# IC_left.net
KiCad netlist of a schematic drawn in Altium Designer
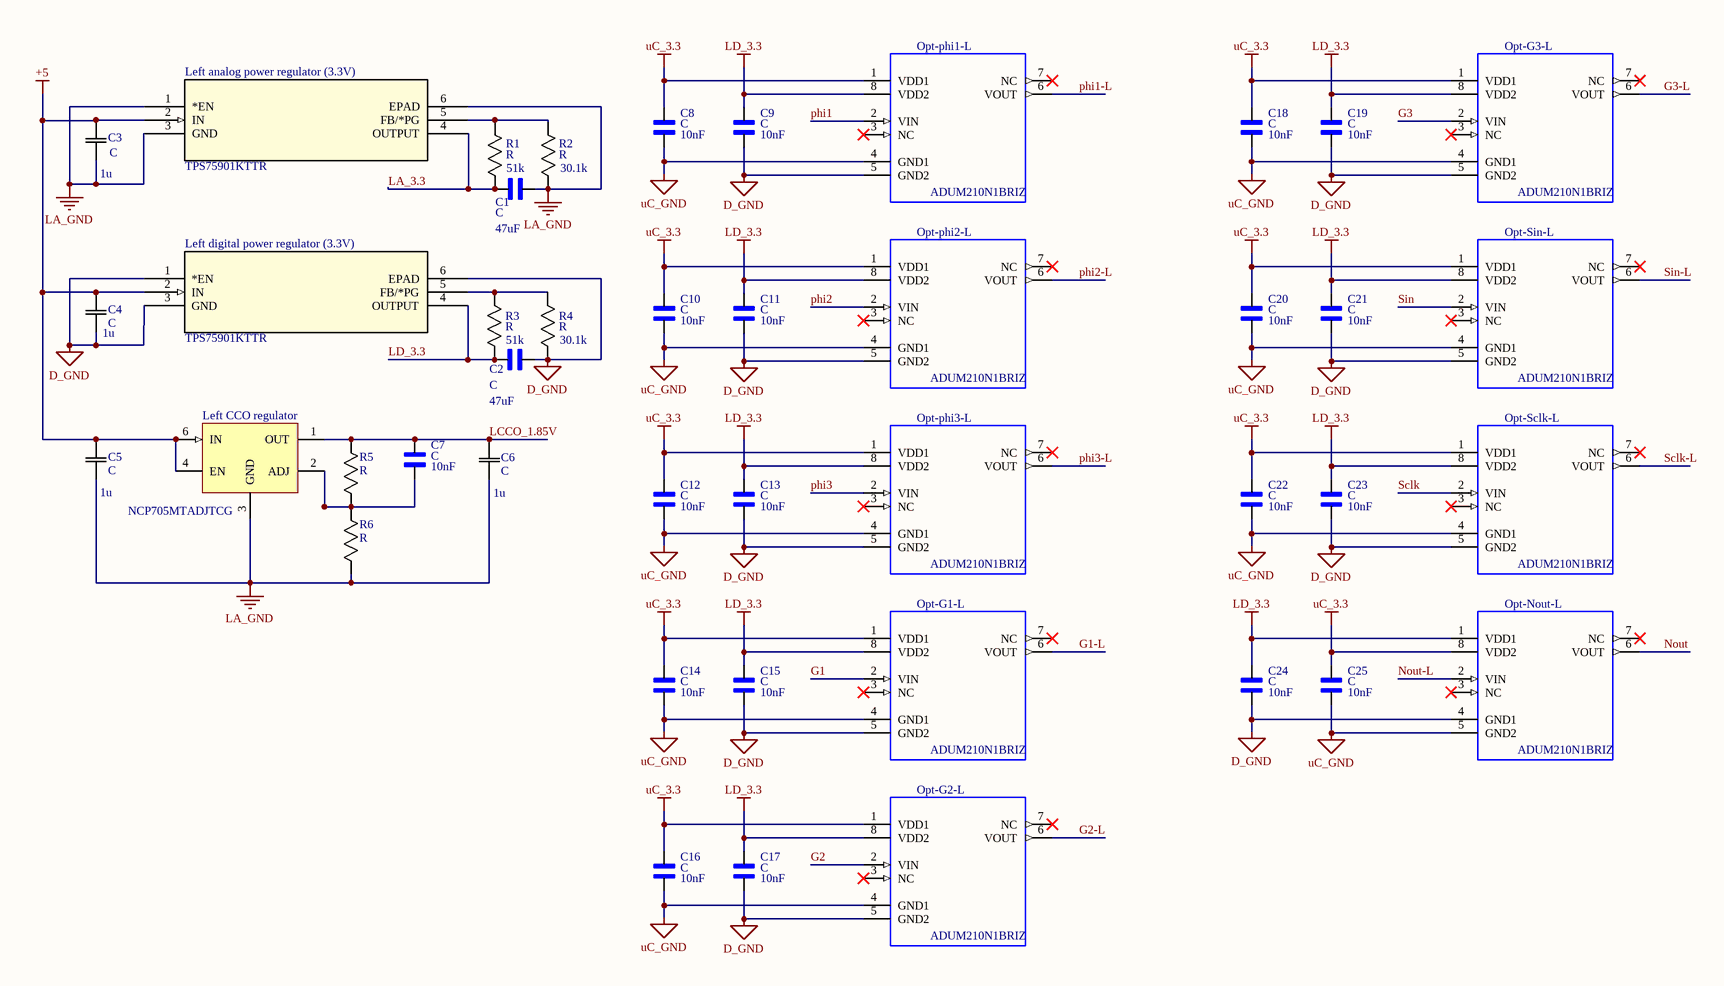
[diagram p0: IC left.SchDoc]

(export (version "E")
  (design (tool "Eeschema 10.0.6"))
  (components
    (comp (ref "C1")
      (value "C")
      (footprint "CAPC1608X9N")
      (description "Multilayer Ceramic Capacitors - 47uF 4V X5R 20% Pad SMD 0603 85C T/R")
      (fields
        (field (name "DIGI-KEY_PART_NUMBER") "490-13246-1-ND")
        (field (name "MF") "Murata")
        (field (name "ALTIUM_VALUE") "47uF")
      )
      (libsource (lib "47uF 0603  CAP") (part "GRM188R60G476ME15D"))
    )
    (comp (ref "C2")
      (value "C")
      (footprint "CAPC1608X9N")
      (description "Multilayer Ceramic Capacitors - 47uF 4V X5R 20% Pad SMD 0603 85C T/R")
      (fields
        (field (name "DIGI-KEY_PART_NUMBER") "490-13246-1-ND")
        (field (name "MF") "Murata")
        (field (name "ALTIUM_VALUE") "47uF")
      )
      (libsource (lib "47uF 0603  CAP") (part "GRM188R60G476ME15D"))
    )
    (comp (ref "C3")
      (value "C")
      (footprint "CAP_GRM_188")
      (description "Imported")
      (fields
        (field (name "ALTIUM_VALUE") "1u")
        (field (name "MANUFACTURER PART NUMBER") "GRM188R60J105KA01D")
      )
      (libsource (lib "1uF 0603 CAP") (part "GRM188R60J105KA0"))
    )
    (comp (ref "C4")
      (value "C")
      (footprint "CAP_GRM_188")
      (description "Imported")
      (fields
        (field (name "ALTIUM_VALUE") "1u")
        (field (name "MANUFACTURER PART NUMBER") "GRM188R60J105KA01D")
      )
      (libsource (lib "1uF 0603 CAP") (part "GRM188R60J105KA0"))
    )
    (comp (ref "C5")
      (value "C")
      (footprint "CAP_GRM_188")
      (description "Imported")
      (fields
        (field (name "ALTIUM_VALUE") "1u")
        (field (name "MANUFACTURER PART NUMBER") "GRM188R60J105KA01D")
      )
      (libsource (lib "1uF 0603 CAP") (part "GRM188R60J105KA0"))
    )
    (comp (ref "C6")
      (value "C")
      (footprint "CAP_GRM_188")
      (description "Imported")
      (fields
        (field (name "ALTIUM_VALUE") "1u")
        (field (name "MANUFACTURER PART NUMBER") "GRM188R60J105KA01D")
      )
      (libsource (lib "1uF 0603 CAP") (part "GRM188R60J105KA0"))
    )
    (comp (ref "C7")
      (value "C")
      (footprint "CAPC1608X9N")
      (description "Multilayer Ceramic Capacitor, GRM Series, 0.01 F, 5%, C0G / NP0, 50 V, 0603 [1608 Metric]")
      (fields
        (field (name "MF") "Murata")
        (field (name "DIGI-KEY_PART_NUMBER") "490-9666-1-ND")
        (field (name "ALTIUM_VALUE") "10nF")
      )
      (libsource (lib "10nF 0603 CAP") (part "GRM1885C1H103JA01D"))
    )
    (comp (ref "C8")
      (value "C")
      (footprint "CAPC1608X9N")
      (description "Multilayer Ceramic Capacitor, GRM Series, 0.01 F, 5%, C0G / NP0, 50 V, 0603 [1608 Metric]")
      (fields
        (field (name "MF") "Murata")
        (field (name "DIGI-KEY_PART_NUMBER") "490-9666-1-ND")
        (field (name "ALTIUM_VALUE") "10nF")
      )
      (libsource (lib "10nF 0603 CAP") (part "GRM1885C1H103JA01D"))
    )
    (comp (ref "C9")
      (value "C")
      (footprint "CAPC1608X9N")
      (description "Multilayer Ceramic Capacitor, GRM Series, 0.01 F, 5%, C0G / NP0, 50 V, 0603 [1608 Metric]")
      (fields
        (field (name "MF") "Murata")
        (field (name "DIGI-KEY_PART_NUMBER") "490-9666-1-ND")
        (field (name "ALTIUM_VALUE") "10nF")
      )
      (libsource (lib "10nF 0603 CAP") (part "GRM1885C1H103JA01D"))
    )
    (comp (ref "C10")
      (value "C")
      (footprint "CAPC1608X9N")
      (description "Multilayer Ceramic Capacitor, GRM Series, 0.01 F, 5%, C0G / NP0, 50 V, 0603 [1608 Metric]")
      (fields
        (field (name "MF") "Murata")
        (field (name "DIGI-KEY_PART_NUMBER") "490-9666-1-ND")
        (field (name "ALTIUM_VALUE") "10nF")
      )
      (libsource (lib "10nF 0603 CAP") (part "GRM1885C1H103JA01D"))
    )
    (comp (ref "C11")
      (value "C")
      (footprint "CAPC1608X9N")
      (description "Multilayer Ceramic Capacitor, GRM Series, 0.01 F, 5%, C0G / NP0, 50 V, 0603 [1608 Metric]")
      (fields
        (field (name "MF") "Murata")
        (field (name "DIGI-KEY_PART_NUMBER") "490-9666-1-ND")
        (field (name "ALTIUM_VALUE") "10nF")
      )
      (libsource (lib "10nF 0603 CAP") (part "GRM1885C1H103JA01D"))
    )
    (comp (ref "C12")
      (value "C")
      (footprint "CAPC1608X9N")
      (description "Multilayer Ceramic Capacitor, GRM Series, 0.01 F, 5%, C0G / NP0, 50 V, 0603 [1608 Metric]")
      (fields
        (field (name "MF") "Murata")
        (field (name "DIGI-KEY_PART_NUMBER") "490-9666-1-ND")
        (field (name "ALTIUM_VALUE") "10nF")
      )
      (libsource (lib "10nF 0603 CAP") (part "GRM1885C1H103JA01D"))
    )
    (comp (ref "C13")
      (value "C")
      (footprint "CAPC1608X9N")
      (description "Multilayer Ceramic Capacitor, GRM Series, 0.01 F, 5%, C0G / NP0, 50 V, 0603 [1608 Metric]")
      (fields
        (field (name "MF") "Murata")
        (field (name "DIGI-KEY_PART_NUMBER") "490-9666-1-ND")
        (field (name "ALTIUM_VALUE") "10nF")
      )
      (libsource (lib "10nF 0603 CAP") (part "GRM1885C1H103JA01D"))
    )
    (comp (ref "C14")
      (value "C")
      (footprint "CAPC1608X9N")
      (description "Multilayer Ceramic Capacitor, GRM Series, 0.01 F, 5%, C0G / NP0, 50 V, 0603 [1608 Metric]")
      (fields
        (field (name "MF") "Murata")
        (field (name "DIGI-KEY_PART_NUMBER") "490-9666-1-ND")
        (field (name "ALTIUM_VALUE") "10nF")
      )
      (libsource (lib "10nF 0603 CAP") (part "GRM1885C1H103JA01D"))
    )
    (comp (ref "C15")
      (value "C")
      (footprint "CAPC1608X9N")
      (description "Multilayer Ceramic Capacitor, GRM Series, 0.01 F, 5%, C0G / NP0, 50 V, 0603 [1608 Metric]")
      (fields
        (field (name "MF") "Murata")
        (field (name "DIGI-KEY_PART_NUMBER") "490-9666-1-ND")
        (field (name "ALTIUM_VALUE") "10nF")
      )
      (libsource (lib "10nF 0603 CAP") (part "GRM1885C1H103JA01D"))
    )
    (comp (ref "C16")
      (value "C")
      (footprint "CAPC1608X9N")
      (description "Multilayer Ceramic Capacitor, GRM Series, 0.01 F, 5%, C0G / NP0, 50 V, 0603 [1608 Metric]")
      (fields
        (field (name "MF") "Murata")
        (field (name "DIGI-KEY_PART_NUMBER") "490-9666-1-ND")
        (field (name "ALTIUM_VALUE") "10nF")
      )
      (libsource (lib "10nF 0603 CAP") (part "GRM1885C1H103JA01D"))
    )
    (comp (ref "C17")
      (value "C")
      (footprint "CAPC1608X9N")
      (description "Multilayer Ceramic Capacitor, GRM Series, 0.01 F, 5%, C0G / NP0, 50 V, 0603 [1608 Metric]")
      (fields
        (field (name "MF") "Murata")
        (field (name "DIGI-KEY_PART_NUMBER") "490-9666-1-ND")
        (field (name "ALTIUM_VALUE") "10nF")
      )
      (libsource (lib "10nF 0603 CAP") (part "GRM1885C1H103JA01D"))
    )
    (comp (ref "C18")
      (value "C")
      (footprint "CAPC1608X9N")
      (description "Multilayer Ceramic Capacitor, GRM Series, 0.01 F, 5%, C0G / NP0, 50 V, 0603 [1608 Metric]")
      (fields
        (field (name "MF") "Murata")
        (field (name "DIGI-KEY_PART_NUMBER") "490-9666-1-ND")
        (field (name "ALTIUM_VALUE") "10nF")
      )
      (libsource (lib "10nF 0603 CAP") (part "GRM1885C1H103JA01D"))
    )
    (comp (ref "C19")
      (value "C")
      (footprint "CAPC1608X9N")
      (description "Multilayer Ceramic Capacitor, GRM Series, 0.01 F, 5%, C0G / NP0, 50 V, 0603 [1608 Metric]")
      (fields
        (field (name "MF") "Murata")
        (field (name "DIGI-KEY_PART_NUMBER") "490-9666-1-ND")
        (field (name "ALTIUM_VALUE") "10nF")
      )
      (libsource (lib "10nF 0603 CAP") (part "GRM1885C1H103JA01D"))
    )
    (comp (ref "C20")
      (value "C")
      (footprint "CAPC1608X9N")
      (description "Multilayer Ceramic Capacitor, GRM Series, 0.01 F, 5%, C0G / NP0, 50 V, 0603 [1608 Metric]")
      (fields
        (field (name "MF") "Murata")
        (field (name "DIGI-KEY_PART_NUMBER") "490-9666-1-ND")
        (field (name "ALTIUM_VALUE") "10nF")
      )
      (libsource (lib "10nF 0603 CAP") (part "GRM1885C1H103JA01D"))
    )
    (comp (ref "C21")
      (value "C")
      (footprint "CAPC1608X9N")
      (description "Multilayer Ceramic Capacitor, GRM Series, 0.01 F, 5%, C0G / NP0, 50 V, 0603 [1608 Metric]")
      (fields
        (field (name "MF") "Murata")
        (field (name "DIGI-KEY_PART_NUMBER") "490-9666-1-ND")
        (field (name "ALTIUM_VALUE") "10nF")
      )
      (libsource (lib "10nF 0603 CAP") (part "GRM1885C1H103JA01D"))
    )
    (comp (ref "C22")
      (value "C")
      (footprint "CAPC1608X9N")
      (description "Multilayer Ceramic Capacitor, GRM Series, 0.01 F, 5%, C0G / NP0, 50 V, 0603 [1608 Metric]")
      (fields
        (field (name "MF") "Murata")
        (field (name "DIGI-KEY_PART_NUMBER") "490-9666-1-ND")
        (field (name "ALTIUM_VALUE") "10nF")
      )
      (libsource (lib "10nF 0603 CAP") (part "GRM1885C1H103JA01D"))
    )
    (comp (ref "C23")
      (value "C")
      (footprint "CAPC1608X9N")
      (description "Multilayer Ceramic Capacitor, GRM Series, 0.01 F, 5%, C0G / NP0, 50 V, 0603 [1608 Metric]")
      (fields
        (field (name "MF") "Murata")
        (field (name "DIGI-KEY_PART_NUMBER") "490-9666-1-ND")
        (field (name "ALTIUM_VALUE") "10nF")
      )
      (libsource (lib "10nF 0603 CAP") (part "GRM1885C1H103JA01D"))
    )
    (comp (ref "C24")
      (value "C")
      (footprint "CAPC1608X9N")
      (description "Multilayer Ceramic Capacitor, GRM Series, 0.01 F, 5%, C0G / NP0, 50 V, 0603 [1608 Metric]")
      (fields
        (field (name "MF") "Murata")
        (field (name "DIGI-KEY_PART_NUMBER") "490-9666-1-ND")
        (field (name "ALTIUM_VALUE") "10nF")
      )
      (libsource (lib "10nF 0603 CAP") (part "GRM1885C1H103JA01D"))
    )
    (comp (ref "C25")
      (value "C")
      (footprint "CAPC1608X9N")
      (description "Multilayer Ceramic Capacitor, GRM Series, 0.01 F, 5%, C0G / NP0, 50 V, 0603 [1608 Metric]")
      (fields
        (field (name "MF") "Murata")
        (field (name "DIGI-KEY_PART_NUMBER") "490-9666-1-ND")
        (field (name "ALTIUM_VALUE") "10nF")
      )
      (libsource (lib "10nF 0603 CAP") (part "GRM1885C1H103JA01D"))
    )
    (comp (ref "Left analog power regulator (3.3V)")
      (value "TPS75901KTTR")
      (footprint "TO-263-5")
      (description "Imported")
      (fields (field (name "MANUFACTURER") "Texas Instruments"))
      (libsource (lib "TPS75901KTTR") (part "TPS75901KTTR"))
    )
    (comp (ref "Left CCO regulator")
      (value "NCP705MTADJTCG")
      (footprint "WDFN6")
      (description "500 mA, Ultra-Low  Quiescent Current, IQ 13 A,  Ultra-Low Noise, LDO  Voltage Regulator")
      (fields (field (name "MANUFACTURER") "ON Semiconductor"))
      (libsource (lib "NCP705MTADJTCG") (part "NCP705MTADJTCG"))
    )
    (comp (ref "Left digital power regulator (3.3V)")
      (value "TPS75901KTTR")
      (footprint "TO-263-5")
      (description "Imported")
      (fields (field (name "MANUFACTURER") "Texas Instruments"))
      (libsource (lib "TPS75901KTTR") (part "TPS75901KTTR"))
    )
    (comp (ref "Opt-G1-L")
      (value "ADUM210N1BRIZ")
      (footprint "SOIC127P1150X330-8N")
      (description "Digital isolator 1-CH 8-Pin SOIC T/R")
      (fields (field (name "DIGI-KEY_PART_NUMBER") "ADUM210N1BRIZ-ND") (field (name "MF") "Analog Devices"))
      (libsource (lib "ADUM210N1BRIZ") (part "ADUM210N1BRIZ"))
    )
    (comp (ref "Opt-G2-L")
      (value "ADUM210N1BRIZ")
      (footprint "SOIC127P1150X330-8N")
      (description "Digital isolator 1-CH 8-Pin SOIC T/R")
      (fields (field (name "DIGI-KEY_PART_NUMBER") "ADUM210N1BRIZ-ND") (field (name "MF") "Analog Devices"))
      (libsource (lib "ADUM210N1BRIZ") (part "ADUM210N1BRIZ"))
    )
    (comp (ref "Opt-G3-L")
      (value "ADUM210N1BRIZ")
      (footprint "SOIC127P1150X330-8N")
      (description "Digital isolator 1-CH 8-Pin SOIC T/R")
      (fields (field (name "DIGI-KEY_PART_NUMBER") "ADUM210N1BRIZ-ND") (field (name "MF") "Analog Devices"))
      (libsource (lib "ADUM210N1BRIZ") (part "ADUM210N1BRIZ"))
    )
    (comp (ref "Opt-Nout-L")
      (value "ADUM210N1BRIZ")
      (footprint "SOIC127P1150X330-8N")
      (description "Digital isolator 1-CH 8-Pin SOIC T/R")
      (fields (field (name "DIGI-KEY_PART_NUMBER") "ADUM210N1BRIZ-ND") (field (name "MF") "Analog Devices"))
      (libsource (lib "ADUM210N1BRIZ") (part "ADUM210N1BRIZ"))
    )
    (comp (ref "Opt-phi1-L")
      (value "ADUM210N1BRIZ")
      (footprint "SOIC127P1150X330-8N")
      (description "Digital isolator 1-CH 8-Pin SOIC T/R")
      (fields (field (name "DIGI-KEY_PART_NUMBER") "ADUM210N1BRIZ-ND") (field (name "MF") "Analog Devices"))
      (libsource (lib "ADUM210N1BRIZ") (part "ADUM210N1BRIZ"))
    )
    (comp (ref "Opt-phi2-L")
      (value "ADUM210N1BRIZ")
      (footprint "SOIC127P1150X330-8N")
      (description "Digital isolator 1-CH 8-Pin SOIC T/R")
      (fields (field (name "DIGI-KEY_PART_NUMBER") "ADUM210N1BRIZ-ND") (field (name "MF") "Analog Devices"))
      (libsource (lib "ADUM210N1BRIZ") (part "ADUM210N1BRIZ"))
    )
    (comp (ref "Opt-phi3-L")
      (value "ADUM210N1BRIZ")
      (footprint "SOIC127P1150X330-8N")
      (description "Digital isolator 1-CH 8-Pin SOIC T/R")
      (fields (field (name "DIGI-KEY_PART_NUMBER") "ADUM210N1BRIZ-ND") (field (name "MF") "Analog Devices"))
      (libsource (lib "ADUM210N1BRIZ") (part "ADUM210N1BRIZ"))
    )
    (comp (ref "Opt-Sclk-L")
      (value "ADUM210N1BRIZ")
      (footprint "SOIC127P1150X330-8N")
      (description "Digital isolator 1-CH 8-Pin SOIC T/R")
      (fields (field (name "DIGI-KEY_PART_NUMBER") "ADUM210N1BRIZ-ND") (field (name "MF") "Analog Devices"))
      (libsource (lib "ADUM210N1BRIZ") (part "ADUM210N1BRIZ"))
    )
    (comp (ref "Opt-Sin-L")
      (value "ADUM210N1BRIZ")
      (footprint "SOIC127P1150X330-8N")
      (description "Digital isolator 1-CH 8-Pin SOIC T/R")
      (fields (field (name "DIGI-KEY_PART_NUMBER") "ADUM210N1BRIZ-ND") (field (name "MF") "Analog Devices"))
      (libsource (lib "ADUM210N1BRIZ") (part "ADUM210N1BRIZ"))
    )
    (comp (ref "R1")
      (value "R")
      (footprint "RES_0816")
      (description "Imported")
      (fields (field (name "ALTIUM_VALUE") "51k") (field (name "MANUFACTURER PART NUMBER") "RR0816P-513-D"))
      (libsource (lib "51kOhm 0603 RES") (part "RR0816P-513-D"))
    )
    (comp (ref "R2")
      (value "R")
      (footprint "RC0603N")
      (description "Imported")
      (fields
        (field (name "ALTIUM_VALUE") "30.1k")
        (field (name "MANUFACTURER PART NUMBER") "RT0603BRD0730K1L")
      )
      (libsource (lib "30.1kOhm 0603 RES") (part "RT0603BRD0730K1L"))
    )
    (comp (ref "R3")
      (value "R")
      (footprint "RES_0816")
      (description "Imported")
      (fields (field (name "ALTIUM_VALUE") "51k") (field (name "MANUFACTURER PART NUMBER") "RR0816P-513-D"))
      (libsource (lib "51kOhm 0603 RES") (part "RR0816P-513-D"))
    )
    (comp (ref "R4")
      (value "R")
      (footprint "RC0603N")
      (description "Imported")
      (fields
        (field (name "ALTIUM_VALUE") "30.1k")
        (field (name "MANUFACTURER PART NUMBER") "RT0603BRD0730K1L")
      )
      (libsource (lib "30.1kOhm 0603 RES") (part "RT0603BRD0730K1L"))
    )
    (comp (ref "R5")
      (value "R")
      (footprint "RC0603N")
      (description "Imported")
      (fields (field (name "MANUFACTURER PART NUMBER") "RC0603FR-07130KL"))
      (libsource (lib "130k 0603 RES") (part "RC0603FR-07130KL"))
    )
    (comp (ref "R6")
      (value "R")
      (footprint "RC0603N")
      (description "Imported")
      (fields (field (name "MANUFACTURER PART NUMBER") "ERJ-3GEY0R00V"))
      (libsource (lib "98.8k 0603 RES") (part "ERJ-3GEY0R00V"))
    )
  )
  (nets
    (net (code "1") (name "+5") (class "Default")
      (node (ref "C3") (pin "2") (pinfunction "2_2") (pintype "passive"))
      (node (ref "C4") (pin "2") (pinfunction "2_2") (pintype "passive"))
      (node (ref "C5") (pin "2") (pinfunction "2_2") (pintype "passive"))
      (node (ref "Left CCO regulator") (pin "4") (pinfunction "EN_4") (pintype "passive"))
      (node (ref "Left CCO regulator") (pin "6") (pinfunction "IN_6") (pintype "input"))
      (node (ref "Left analog power regulator (3.3V)") (pin "2") (pinfunction "IN_2") (pintype "input"))
      (node (ref "Left digital power regulator (3.3V)") (pin "2") (pinfunction "IN_2") (pintype "input"))
    )
    (net (code "2") (name "/G1") (class "Default")
      (node (ref "Opt-G1-L") (pin "2") (pinfunction "VIN_2") (pintype "input"))
    )
    (net (code "3") (name "/G1-L") (class "Default")
      (node (ref "Opt-G1-L") (pin "6") (pinfunction "VOUT_6") (pintype "output"))
    )
    (net (code "4") (name "/G2") (class "Default")
      (node (ref "Opt-G2-L") (pin "2") (pinfunction "VIN_2") (pintype "input"))
    )
    (net (code "5") (name "/G2-L") (class "Default")
      (node (ref "Opt-G2-L") (pin "6") (pinfunction "VOUT_6") (pintype "output"))
    )
    (net (code "6") (name "/G3") (class "Default")
      (node (ref "Opt-G3-L") (pin "2") (pinfunction "VIN_2") (pintype "input"))
    )
    (net (code "7") (name "/G3-L") (class "Default")
      (node (ref "Opt-G3-L") (pin "6") (pinfunction "VOUT_6") (pintype "output"))
    )
    (net (code "8") (name "/LA_3.3") (class "Default")
      (node (ref "C1") (pin "2") (pinfunction "2_2") (pintype "passive"))
      (node (ref "Left analog power regulator (3.3V)") (pin "4") (pinfunction "OUTPUT_4") (pintype "power_in"))
      (node (ref "R1") (pin "1") (pinfunction "1_1") (pintype "passive"))
    )
    (net (code "9") (name "/LCCO_1.85V") (class "Default")
      (node (ref "C6") (pin "2") (pinfunction "2_2") (pintype "passive"))
      (node (ref "C7") (pin "1") (pinfunction "1_1") (pintype "passive"))
      (node (ref "Left CCO regulator") (pin "1") (pinfunction "OUT_1") (pintype "power_in"))
      (node (ref "R5") (pin "1") (pinfunction "1_1") (pintype "passive"))
    )
    (net (code "10") (name "/Nout") (class "Default")
      (node (ref "Opt-Nout-L") (pin "6") (pinfunction "VOUT_6") (pintype "output"))
    )
    (net (code "11") (name "/Nout-L") (class "Default")
      (node (ref "Opt-Nout-L") (pin "2") (pinfunction "VIN_2") (pintype "input"))
    )
    (net (code "12") (name "/Sclk") (class "Default")
      (node (ref "Opt-Sclk-L") (pin "2") (pinfunction "VIN_2") (pintype "input"))
    )
    (net (code "13") (name "/Sclk-L") (class "Default")
      (node (ref "Opt-Sclk-L") (pin "6") (pinfunction "VOUT_6") (pintype "output"))
    )
    (net (code "14") (name "/Sin") (class "Default")
      (node (ref "Opt-Sin-L") (pin "2") (pinfunction "VIN_2") (pintype "input"))
    )
    (net (code "15") (name "/Sin-L") (class "Default")
      (node (ref "Opt-Sin-L") (pin "6") (pinfunction "VOUT_6") (pintype "output"))
    )
    (net (code "16") (name "/phi1") (class "Default")
      (node (ref "Opt-phi1-L") (pin "2") (pinfunction "VIN_2") (pintype "input"))
    )
    (net (code "17") (name "/phi1-L") (class "Default")
      (node (ref "Opt-phi1-L") (pin "6") (pinfunction "VOUT_6") (pintype "output"))
    )
    (net (code "18") (name "/phi2") (class "Default")
      (node (ref "Opt-phi2-L") (pin "2") (pinfunction "VIN_2") (pintype "input"))
    )
    (net (code "19") (name "/phi2-L") (class "Default")
      (node (ref "Opt-phi2-L") (pin "6") (pinfunction "VOUT_6") (pintype "output"))
    )
    (net (code "20") (name "/phi3") (class "Default")
      (node (ref "Opt-phi3-L") (pin "2") (pinfunction "VIN_2") (pintype "input"))
    )
    (net (code "21") (name "/phi3-L") (class "Default")
      (node (ref "Opt-phi3-L") (pin "6") (pinfunction "VOUT_6") (pintype "output"))
    )
    (net (code "22") (name "D_GND") (class "Default")
      (node (ref "C11") (pin "2") (pinfunction "2_2") (pintype "passive"))
      (node (ref "C13") (pin "2") (pinfunction "2_2") (pintype "passive"))
      (node (ref "C15") (pin "2") (pinfunction "2_2") (pintype "passive"))
      (node (ref "C17") (pin "2") (pinfunction "2_2") (pintype "passive"))
      (node (ref "C19") (pin "2") (pinfunction "2_2") (pintype "passive"))
      (node (ref "C2") (pin "1") (pinfunction "1_1") (pintype "passive"))
      (node (ref "C21") (pin "2") (pinfunction "2_2") (pintype "passive"))
      (node (ref "C23") (pin "2") (pinfunction "2_2") (pintype "passive"))
      (node (ref "C24") (pin "2") (pinfunction "2_2") (pintype "passive"))
      (node (ref "C4") (pin "1") (pinfunction "1_1") (pintype "passive"))
      (node (ref "C9") (pin "2") (pinfunction "2_2") (pintype "passive"))
      (node (ref "Left digital power regulator (3.3V)") (pin "1") (pinfunction "*EN_1") (pintype "passive"))
      (node (ref "Left digital power regulator (3.3V)") (pin "3") (pinfunction "GND_3") (pintype "power_in"))
      (node (ref "Left digital power regulator (3.3V)") (pin "6") (pinfunction "EPAD_6") (pintype "passive"))
      (node (ref "Opt-G1-L") (pin "5") (pinfunction "GND2_5") (pintype "passive"))
      (node (ref "Opt-G2-L") (pin "5") (pinfunction "GND2_5") (pintype "passive"))
      (node (ref "Opt-G3-L") (pin "5") (pinfunction "GND2_5") (pintype "passive"))
      (node (ref "Opt-Nout-L") (pin "4") (pinfunction "GND1_4") (pintype "passive"))
      (node (ref "Opt-Sclk-L") (pin "5") (pinfunction "GND2_5") (pintype "passive"))
      (node (ref "Opt-Sin-L") (pin "5") (pinfunction "GND2_5") (pintype "passive"))
      (node (ref "Opt-phi1-L") (pin "5") (pinfunction "GND2_5") (pintype "passive"))
      (node (ref "Opt-phi2-L") (pin "5") (pinfunction "GND2_5") (pintype "passive"))
      (node (ref "Opt-phi3-L") (pin "5") (pinfunction "GND2_5") (pintype "passive"))
      (node (ref "R4") (pin "2") (pinfunction "2_2") (pintype "passive"))
    )
    (net (code "23") (name "LA_GND") (class "Default")
      (node (ref "C1") (pin "1") (pinfunction "1_1") (pintype "passive"))
      (node (ref "C3") (pin "1") (pinfunction "1_1") (pintype "passive"))
      (node (ref "C5") (pin "1") (pinfunction "1_1") (pintype "passive"))
      (node (ref "C6") (pin "1") (pinfunction "1_1") (pintype "passive"))
      (node (ref "Left CCO regulator") (pin "3") (pinfunction "GND_3") (pintype "power_in"))
      (node (ref "Left analog power regulator (3.3V)") (pin "1") (pinfunction "*EN_1") (pintype "passive"))
      (node (ref "Left analog power regulator (3.3V)") (pin "3") (pinfunction "GND_3") (pintype "power_in"))
      (node (ref "Left analog power regulator (3.3V)") (pin "6") (pinfunction "EPAD_6") (pintype "passive"))
      (node (ref "R2") (pin "2") (pinfunction "2_2") (pintype "passive"))
      (node (ref "R6") (pin "2") (pinfunction "2_2") (pintype "passive"))
    )
    (net (code "24") (name "LD_3.3") (class "Default")
      (node (ref "C11") (pin "1") (pinfunction "1_1") (pintype "passive"))
      (node (ref "C13") (pin "1") (pinfunction "1_1") (pintype "passive"))
      (node (ref "C15") (pin "1") (pinfunction "1_1") (pintype "passive"))
      (node (ref "C17") (pin "1") (pinfunction "1_1") (pintype "passive"))
      (node (ref "C19") (pin "1") (pinfunction "1_1") (pintype "passive"))
      (node (ref "C2") (pin "2") (pinfunction "2_2") (pintype "passive"))
      (node (ref "C21") (pin "1") (pinfunction "1_1") (pintype "passive"))
      (node (ref "C23") (pin "1") (pinfunction "1_1") (pintype "passive"))
      (node (ref "C24") (pin "1") (pinfunction "1_1") (pintype "passive"))
      (node (ref "C9") (pin "1") (pinfunction "1_1") (pintype "passive"))
      (node (ref "Left digital power regulator (3.3V)") (pin "4") (pinfunction "OUTPUT_4") (pintype "power_in"))
      (node (ref "Opt-G1-L") (pin "8") (pinfunction "VDD2_8") (pintype "power_in"))
      (node (ref "Opt-G2-L") (pin "8") (pinfunction "VDD2_8") (pintype "power_in"))
      (node (ref "Opt-G3-L") (pin "8") (pinfunction "VDD2_8") (pintype "power_in"))
      (node (ref "Opt-Nout-L") (pin "1") (pinfunction "VDD1_1") (pintype "power_in"))
      (node (ref "Opt-Sclk-L") (pin "8") (pinfunction "VDD2_8") (pintype "power_in"))
      (node (ref "Opt-Sin-L") (pin "8") (pinfunction "VDD2_8") (pintype "power_in"))
      (node (ref "Opt-phi1-L") (pin "8") (pinfunction "VDD2_8") (pintype "power_in"))
      (node (ref "Opt-phi2-L") (pin "8") (pinfunction "VDD2_8") (pintype "power_in"))
      (node (ref "Opt-phi3-L") (pin "8") (pinfunction "VDD2_8") (pintype "power_in"))
      (node (ref "R3") (pin "1") (pinfunction "1_1") (pintype "passive"))
    )
    (net (code "25") (name "Net-(Left CCO regulator-ADJ)") (class "Default")
      (node (ref "C7") (pin "2") (pinfunction "2_2") (pintype "passive"))
      (node (ref "Left CCO regulator") (pin "2") (pinfunction "ADJ_2") (pintype "passive"))
      (node (ref "R5") (pin "2") (pinfunction "2_2") (pintype "passive"))
      (node (ref "R6") (pin "1") (pinfunction "1_1") (pintype "passive"))
    )
    (net (code "26") (name "Net-(Left analog power regulator (3.3V)-FB{slash}*PG)") (class "Default")
      (node (ref "Left analog power regulator (3.3V)") (pin "5") (pinfunction "FB/*PG_5") (pintype "passive"))
      (node (ref "R1") (pin "2") (pinfunction "2_2") (pintype "passive"))
      (node (ref "R2") (pin "1") (pinfunction "1_1") (pintype "passive"))
    )
    (net (code "27") (name "Net-(Left digital power regulator (3.3V)-FB{slash}*PG)") (class "Default")
      (node (ref "Left digital power regulator (3.3V)") (pin "5") (pinfunction "FB/*PG_5") (pintype "passive"))
      (node (ref "R3") (pin "2") (pinfunction "2_2") (pintype "passive"))
      (node (ref "R4") (pin "1") (pinfunction "1_1") (pintype "passive"))
    )
    (net (code "28") (name "uC_3.3") (class "Default")
      (node (ref "C10") (pin "1") (pinfunction "1_1") (pintype "passive"))
      (node (ref "C12") (pin "1") (pinfunction "1_1") (pintype "passive"))
      (node (ref "C14") (pin "1") (pinfunction "1_1") (pintype "passive"))
      (node (ref "C16") (pin "1") (pinfunction "1_1") (pintype "passive"))
      (node (ref "C18") (pin "1") (pinfunction "1_1") (pintype "passive"))
      (node (ref "C20") (pin "1") (pinfunction "1_1") (pintype "passive"))
      (node (ref "C22") (pin "1") (pinfunction "1_1") (pintype "passive"))
      (node (ref "C25") (pin "1") (pinfunction "1_1") (pintype "passive"))
      (node (ref "C8") (pin "1") (pinfunction "1_1") (pintype "passive"))
      (node (ref "Opt-G1-L") (pin "1") (pinfunction "VDD1_1") (pintype "power_in"))
      (node (ref "Opt-G2-L") (pin "1") (pinfunction "VDD1_1") (pintype "power_in"))
      (node (ref "Opt-G3-L") (pin "1") (pinfunction "VDD1_1") (pintype "power_in"))
      (node (ref "Opt-Nout-L") (pin "8") (pinfunction "VDD2_8") (pintype "power_in"))
      (node (ref "Opt-Sclk-L") (pin "1") (pinfunction "VDD1_1") (pintype "power_in"))
      (node (ref "Opt-Sin-L") (pin "1") (pinfunction "VDD1_1") (pintype "power_in"))
      (node (ref "Opt-phi1-L") (pin "1") (pinfunction "VDD1_1") (pintype "power_in"))
      (node (ref "Opt-phi2-L") (pin "1") (pinfunction "VDD1_1") (pintype "power_in"))
      (node (ref "Opt-phi3-L") (pin "1") (pinfunction "VDD1_1") (pintype "power_in"))
    )
    (net (code "29") (name "uC_GND") (class "Default")
      (node (ref "C10") (pin "2") (pinfunction "2_2") (pintype "passive"))
      (node (ref "C12") (pin "2") (pinfunction "2_2") (pintype "passive"))
      (node (ref "C14") (pin "2") (pinfunction "2_2") (pintype "passive"))
      (node (ref "C16") (pin "2") (pinfunction "2_2") (pintype "passive"))
      (node (ref "C18") (pin "2") (pinfunction "2_2") (pintype "passive"))
      (node (ref "C20") (pin "2") (pinfunction "2_2") (pintype "passive"))
      (node (ref "C22") (pin "2") (pinfunction "2_2") (pintype "passive"))
      (node (ref "C25") (pin "2") (pinfunction "2_2") (pintype "passive"))
      (node (ref "C8") (pin "2") (pinfunction "2_2") (pintype "passive"))
      (node (ref "Opt-G1-L") (pin "4") (pinfunction "GND1_4") (pintype "passive"))
      (node (ref "Opt-G2-L") (pin "4") (pinfunction "GND1_4") (pintype "passive"))
      (node (ref "Opt-G3-L") (pin "4") (pinfunction "GND1_4") (pintype "passive"))
      (node (ref "Opt-Nout-L") (pin "5") (pinfunction "GND2_5") (pintype "passive"))
      (node (ref "Opt-Sclk-L") (pin "4") (pinfunction "GND1_4") (pintype "passive"))
      (node (ref "Opt-Sin-L") (pin "4") (pinfunction "GND1_4") (pintype "passive"))
      (node (ref "Opt-phi1-L") (pin "4") (pinfunction "GND1_4") (pintype "passive"))
      (node (ref "Opt-phi2-L") (pin "4") (pinfunction "GND1_4") (pintype "passive"))
      (node (ref "Opt-phi3-L") (pin "4") (pinfunction "GND1_4") (pintype "passive"))
    )
    (net (code "30") (name "unconnected-(Opt-G1-L-NC-Pad3)") (class "Default")
      (node (ref "Opt-G1-L") (pin "3") (pinfunction "NC_3") (pintype "input+no_connect"))
    )
    (net (code "31") (name "unconnected-(Opt-G1-L-NC-Pad7)") (class "Default")
      (node (ref "Opt-G1-L") (pin "7") (pinfunction "NC_7") (pintype "output+no_connect"))
    )
    (net (code "32") (name "unconnected-(Opt-G2-L-NC-Pad3)") (class "Default")
      (node (ref "Opt-G2-L") (pin "3") (pinfunction "NC_3") (pintype "input+no_connect"))
    )
    (net (code "33") (name "unconnected-(Opt-G2-L-NC-Pad7)") (class "Default")
      (node (ref "Opt-G2-L") (pin "7") (pinfunction "NC_7") (pintype "output+no_connect"))
    )
    (net (code "34") (name "unconnected-(Opt-G3-L-NC-Pad3)") (class "Default")
      (node (ref "Opt-G3-L") (pin "3") (pinfunction "NC_3") (pintype "input+no_connect"))
    )
    (net (code "35") (name "unconnected-(Opt-G3-L-NC-Pad7)") (class "Default")
      (node (ref "Opt-G3-L") (pin "7") (pinfunction "NC_7") (pintype "output+no_connect"))
    )
    (net (code "36") (name "unconnected-(Opt-Nout-L-NC-Pad3)") (class "Default")
      (node (ref "Opt-Nout-L") (pin "3") (pinfunction "NC_3") (pintype "input+no_connect"))
    )
    (net (code "37") (name "unconnected-(Opt-Nout-L-NC-Pad7)") (class "Default")
      (node (ref "Opt-Nout-L") (pin "7") (pinfunction "NC_7") (pintype "output+no_connect"))
    )
    (net (code "38") (name "unconnected-(Opt-Sclk-L-NC-Pad3)") (class "Default")
      (node (ref "Opt-Sclk-L") (pin "3") (pinfunction "NC_3") (pintype "input+no_connect"))
    )
    (net (code "39") (name "unconnected-(Opt-Sclk-L-NC-Pad7)") (class "Default")
      (node (ref "Opt-Sclk-L") (pin "7") (pinfunction "NC_7") (pintype "output+no_connect"))
    )
    (net (code "40") (name "unconnected-(Opt-Sin-L-NC-Pad3)") (class "Default")
      (node (ref "Opt-Sin-L") (pin "3") (pinfunction "NC_3") (pintype "input+no_connect"))
    )
    (net (code "41") (name "unconnected-(Opt-Sin-L-NC-Pad7)") (class "Default")
      (node (ref "Opt-Sin-L") (pin "7") (pinfunction "NC_7") (pintype "output+no_connect"))
    )
    (net (code "42") (name "unconnected-(Opt-phi1-L-NC-Pad3)") (class "Default")
      (node (ref "Opt-phi1-L") (pin "3") (pinfunction "NC_3") (pintype "input+no_connect"))
    )
    (net (code "43") (name "unconnected-(Opt-phi1-L-NC-Pad7)") (class "Default")
      (node (ref "Opt-phi1-L") (pin "7") (pinfunction "NC_7") (pintype "output+no_connect"))
    )
    (net (code "44") (name "unconnected-(Opt-phi2-L-NC-Pad3)") (class "Default")
      (node (ref "Opt-phi2-L") (pin "3") (pinfunction "NC_3") (pintype "input+no_connect"))
    )
    (net (code "45") (name "unconnected-(Opt-phi2-L-NC-Pad7)") (class "Default")
      (node (ref "Opt-phi2-L") (pin "7") (pinfunction "NC_7") (pintype "output+no_connect"))
    )
    (net (code "46") (name "unconnected-(Opt-phi3-L-NC-Pad3)") (class "Default")
      (node (ref "Opt-phi3-L") (pin "3") (pinfunction "NC_3") (pintype "input+no_connect"))
    )
    (net (code "47") (name "unconnected-(Opt-phi3-L-NC-Pad7)") (class "Default")
      (node (ref "Opt-phi3-L") (pin "7") (pinfunction "NC_7") (pintype "output+no_connect"))
    )
  )
)
